# ChessMateBattery.net
KiCad netlist of a schematic drawn in EAGLE
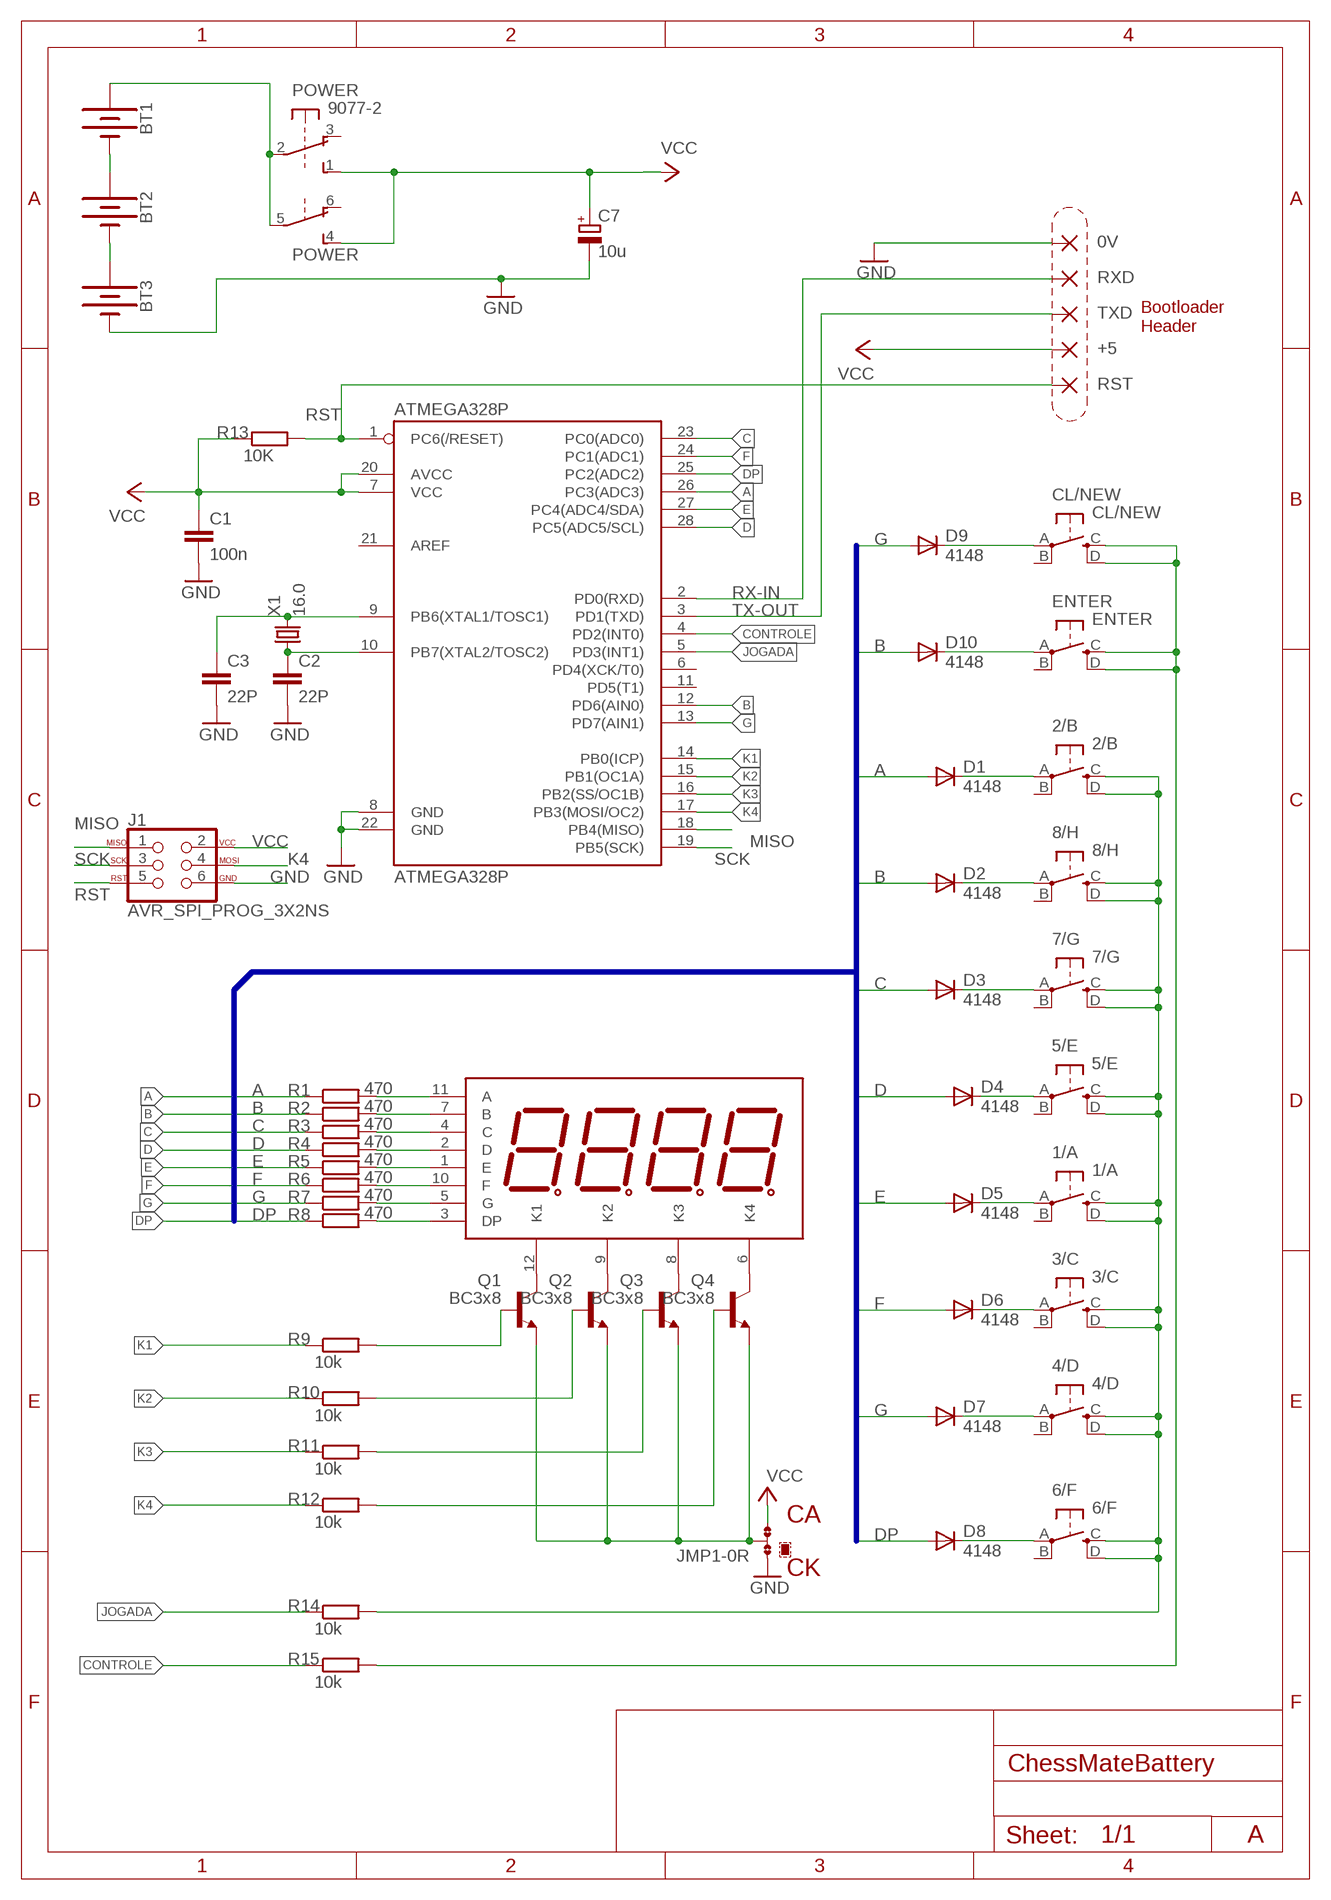
[diagram p0: schematic, sheet 1]

(export (version "E")
  (design (tool "Eeschema 10.0.6"))
  (components
    (comp (ref "+5")
      (value "2,15/1,0")
      (footprint "eagle-import:2,15_1,0")
      (libsource (lib "eagle-import") (part "2,15/1,0"))
    )
    (comp (ref "0V")
      (value "2,15/1,0")
      (footprint "eagle-import:2,15_1,0")
      (libsource (lib "eagle-import") (part "2,15/1,0"))
    )
    (comp (ref "1/A")
      (value "1/A")
      (footprint "eagle-import:TACT_SW")
      (libsource (lib "eagle-import") (part "10-XXTACT"))
    )
    (comp (ref "2/B")
      (value "2/B")
      (footprint "eagle-import:TACT_SW")
      (libsource (lib "eagle-import") (part "10-XXTACT"))
    )
    (comp (ref "3/C")
      (value "3/C")
      (footprint "eagle-import:TACT_SW")
      (libsource (lib "eagle-import") (part "10-XXTACT"))
    )
    (comp (ref "4/D")
      (value "4/D")
      (footprint "eagle-import:TACT_SW")
      (libsource (lib "eagle-import") (part "10-XXTACT"))
    )
    (comp (ref "5/E")
      (value "5/E")
      (footprint "eagle-import:TACT_SW")
      (libsource (lib "eagle-import") (part "10-XXTACT"))
    )
    (comp (ref "6/F")
      (value "6/F")
      (footprint "eagle-import:TACT_SW")
      (libsource (lib "eagle-import") (part "10-XXTACT"))
    )
    (comp (ref "7/G")
      (value "7/G")
      (footprint "eagle-import:TACT_SW")
      (libsource (lib "eagle-import") (part "10-XXTACT"))
    )
    (comp (ref "8/H")
      (value "8/H")
      (footprint "eagle-import:TACT_SW")
      (libsource (lib "eagle-import") (part "10-XXTACT"))
    )
    (comp (ref "ATMEGA328P")
      (value "ATMEGA328P")
      (footprint "eagle-import:DIL28-3")
      (libsource (lib "eagle-import") (part "ATMEGA328P_PDIP"))
    )
    (comp (ref "BT1")
      (value "BATTERY-AAA_KIT")
      (footprint "eagle-import:BATTERY-AAA-KIT")
      (libsource (lib "eagle-import") (part "BATTERY-AAA_KIT"))
    )
    (comp (ref "BT2")
      (value "BATTERY-AAA_KIT")
      (footprint "eagle-import:BATTERY-AAA-KIT")
      (libsource (lib "eagle-import") (part "BATTERY-AAA_KIT"))
    )
    (comp (ref "BT3")
      (value "BATTERY-AAA_KIT")
      (footprint "eagle-import:BATTERY-AAA-KIT")
      (libsource (lib "eagle-import") (part "BATTERY-AAA_KIT"))
    )
    (comp (ref "C1")
      (value "100n")
      (footprint "eagle-import:C050-024X044L")
      (libsource (lib "eagle-import") (part "C-EUC050-024X044L"))
    )
    (comp (ref "C2")
      (value "22P")
      (footprint "eagle-import:C025-024X044L")
      (libsource (lib "eagle-import") (part "C-EU"))
    )
    (comp (ref "C3")
      (value "22P")
      (footprint "eagle-import:C025-024X044L")
      (libsource (lib "eagle-import") (part "C-EU"))
    )
    (comp (ref "C7")
      (value "10u")
      (footprint "eagle-import:TT2D7L")
      (libsource (lib "eagle-import") (part "CPOL-EUTT2D7L"))
    )
    (comp (ref "CL/NEW")
      (value "CL/NEW")
      (footprint "eagle-import:TACT_SW")
      (libsource (lib "eagle-import") (part "10-XXTACT"))
    )
    (comp (ref "D1")
      (value "4148")
      (footprint "eagle-import:DO35-7")
      (libsource (lib "eagle-import") (part "1N4148DO35-7"))
    )
    (comp (ref "D2")
      (value "4148")
      (footprint "eagle-import:DO35-7")
      (libsource (lib "eagle-import") (part "1N4148DO35-7"))
    )
    (comp (ref "D3")
      (value "4148")
      (footprint "eagle-import:DO35-7")
      (libsource (lib "eagle-import") (part "1N4148DO35-7"))
    )
    (comp (ref "D4")
      (value "4148")
      (footprint "eagle-import:DO35-7")
      (libsource (lib "eagle-import") (part "1N4148DO35-7"))
    )
    (comp (ref "D5")
      (value "4148")
      (footprint "eagle-import:DO35-7")
      (libsource (lib "eagle-import") (part "1N4148DO35-7"))
    )
    (comp (ref "D6")
      (value "4148")
      (footprint "eagle-import:DO35-7")
      (libsource (lib "eagle-import") (part "1N4148DO35-7"))
    )
    (comp (ref "D7")
      (value "4148")
      (footprint "eagle-import:DO35-7")
      (libsource (lib "eagle-import") (part "1N4148DO35-7"))
    )
    (comp (ref "D8")
      (value "4148")
      (footprint "eagle-import:DO35-7")
      (libsource (lib "eagle-import") (part "1N4148DO35-7"))
    )
    (comp (ref "D9")
      (value "4148")
      (footprint "eagle-import:DO35-7")
      (libsource (lib "eagle-import") (part "1N4148DO35-7"))
    )
    (comp (ref "D10")
      (value "4148")
      (footprint "eagle-import:DO35-7")
      (libsource (lib "eagle-import") (part "1N4148DO35-7"))
    )
    (comp (ref "DISPLAY")
      (value "4_DIGIT-TOF3461BH-N")
      (footprint "eagle-import:TOF3461BH-N")
      (libsource (lib "eagle-import") (part "4_DIGIT-TOF3461BH-N"))
    )
    (comp (ref "ENTER")
      (value "ENTER")
      (footprint "eagle-import:TACT_SW")
      (libsource (lib "eagle-import") (part "10-XXTACT"))
    )
    (comp (ref "J1")
      (value "AVR_SPI_PROG_3X2NS")
      (footprint "eagle-import:2X3-NS")
      (libsource (lib "eagle-import") (part "AVR_SPI_PROG_3X2NS"))
    )
    (comp (ref "JMP1")
      (value "0R-JUMPA")
      (footprint "eagle-import:A0R-JMP")
      (libsource (lib "eagle-import") (part "0R-JUMPA"))
    )
    (comp (ref "POWER")
      (value "9077-2")
      (footprint "eagle-import:9077-2")
      (libsource (lib "eagle-import") (part "9077-2"))
    )
    (comp (ref "Q1")
      (value "BC3x8")
      (footprint "eagle-import:TO92-EBC")
      (libsource (lib "eagle-import") (part "BC338"))
    )
    (comp (ref "Q2")
      (value "BC3x8")
      (footprint "eagle-import:TO92-EBC")
      (libsource (lib "eagle-import") (part "BC338"))
    )
    (comp (ref "Q3")
      (value "BC3x8")
      (footprint "eagle-import:TO92-EBC")
      (libsource (lib "eagle-import") (part "BC338"))
    )
    (comp (ref "Q4")
      (value "BC3x8")
      (footprint "eagle-import:TO92-EBC")
      (libsource (lib "eagle-import") (part "BC338"))
    )
    (comp (ref "R1")
      (value "470")
      (footprint "eagle-import:0204_7L")
      (libsource (lib "eagle-import") (part "R-EU_0204/7L"))
    )
    (comp (ref "R2")
      (value "470")
      (footprint "eagle-import:0204_7L")
      (libsource (lib "eagle-import") (part "R-EU_0204/7L"))
    )
    (comp (ref "R3")
      (value "470")
      (footprint "eagle-import:0204_7L")
      (libsource (lib "eagle-import") (part "R-EU_0204/7L"))
    )
    (comp (ref "R4")
      (value "470")
      (footprint "eagle-import:0204_7L")
      (libsource (lib "eagle-import") (part "R-EU_0204/7L"))
    )
    (comp (ref "R5")
      (value "470")
      (footprint "eagle-import:0204_7L")
      (libsource (lib "eagle-import") (part "R-EU_0204/7L"))
    )
    (comp (ref "R6")
      (value "470")
      (footprint "eagle-import:0204_7L")
      (libsource (lib "eagle-import") (part "R-EU_0204/7L"))
    )
    (comp (ref "R7")
      (value "470")
      (footprint "eagle-import:0204_7L")
      (libsource (lib "eagle-import") (part "R-EU_0204/7L"))
    )
    (comp (ref "R8")
      (value "470")
      (footprint "eagle-import:0204_7L")
      (libsource (lib "eagle-import") (part "R-EU_0204/7L"))
    )
    (comp (ref "R9")
      (value "10k")
      (footprint "eagle-import:0204_7L")
      (libsource (lib "eagle-import") (part "R-EU_0204/7L"))
    )
    (comp (ref "R10")
      (value "10k")
      (footprint "eagle-import:0204_7L")
      (libsource (lib "eagle-import") (part "R-EU_0204/7L"))
    )
    (comp (ref "R11")
      (value "10k")
      (footprint "eagle-import:0204_7L")
      (libsource (lib "eagle-import") (part "R-EU_0204/7L"))
    )
    (comp (ref "R12")
      (value "10k")
      (footprint "eagle-import:0204_7L")
      (libsource (lib "eagle-import") (part "R-EU_0204/7L"))
    )
    (comp (ref "R13")
      (value "10K")
      (footprint "eagle-import:0204_5L")
      (libsource (lib "eagle-import") (part "R-EU_0204/5L"))
    )
    (comp (ref "R14")
      (value "10k")
      (footprint "eagle-import:0204_7L")
      (libsource (lib "eagle-import") (part "R-EU_0204/7L"))
    )
    (comp (ref "R15")
      (value "10k")
      (footprint "eagle-import:0204_7L")
      (libsource (lib "eagle-import") (part "R-EU_0204/7L"))
    )
    (comp (ref "RST")
      (value "2,15/1,0")
      (footprint "eagle-import:2,15_1,0")
      (libsource (lib "eagle-import") (part "2,15/1,0"))
    )
    (comp (ref "RXD")
      (value "2,15/1,0")
      (footprint "eagle-import:2,15_1,0")
      (libsource (lib "eagle-import") (part "2,15/1,0"))
    )
    (comp (ref "TXD")
      (value "2,15/1,0")
      (footprint "eagle-import:2,15_1,0")
      (libsource (lib "eagle-import") (part "2,15/1,0"))
    )
    (comp (ref "X1")
      (value "16.0")
      (footprint "eagle-import:HC49_SL")
      (libsource (lib "eagle-import") (part "CRYSTALHC49/SL"))
    )
  )
  (nets
    (net (code "1") (name "/MISO") (class "Default")
      (node (ref "ATMEGA328P") (pin "18") (pinfunction "PB4(MISO)_18") (pintype "bidirectional"))
      (node (ref "J1") (pin "1") (pinfunction "1_1") (pintype "passive"))
    )
    (net (code "2") (name "/RST") (class "Default")
      (node (ref "ATMEGA328P") (pin "1") (pinfunction "PC6(/RESET)_1") (pintype "bidirectional"))
      (node (ref "J1") (pin "5") (pinfunction "5_5") (pintype "passive"))
      (node (ref "R13") (pin "2") (pinfunction "2_2") (pintype "passive"))
      (node (ref "RST") (pin "1") (pinfunction "P_1") (pintype "passive"))
    )
    (net (code "3") (name "/RX-IN") (class "Default")
      (node (ref "ATMEGA328P") (pin "2") (pinfunction "PD0(RXD)_2") (pintype "bidirectional"))
      (node (ref "RXD") (pin "1") (pinfunction "P_1") (pintype "passive"))
    )
    (net (code "4") (name "/SCK") (class "Default")
      (node (ref "ATMEGA328P") (pin "19") (pinfunction "PB5(SCK)_19") (pintype "bidirectional"))
      (node (ref "J1") (pin "3") (pinfunction "3_3") (pintype "passive"))
    )
    (net (code "5") (name "/TX-OUT") (class "Default")
      (node (ref "ATMEGA328P") (pin "3") (pinfunction "PD1(TXD)_3") (pintype "bidirectional"))
      (node (ref "TXD") (pin "1") (pinfunction "P_1") (pintype "passive"))
    )
    (net (code "6") (name "A") (class "Default")
      (node (ref "ATMEGA328P") (pin "26") (pinfunction "PC3(ADC3)_26") (pintype "bidirectional"))
      (node (ref "D1") (pin "A") (pinfunction "A_A") (pintype "passive"))
      (node (ref "R1") (pin "1") (pinfunction "1_1") (pintype "passive"))
    )
    (net (code "7") (name "B") (class "Default")
      (node (ref "ATMEGA328P") (pin "12") (pinfunction "PD6(AIN0)_12") (pintype "bidirectional"))
      (node (ref "D10") (pin "A") (pinfunction "A_A") (pintype "passive"))
      (node (ref "D2") (pin "A") (pinfunction "A_A") (pintype "passive"))
      (node (ref "R2") (pin "1") (pinfunction "1_1") (pintype "passive"))
    )
    (net (code "8") (name "C") (class "Default")
      (node (ref "ATMEGA328P") (pin "23") (pinfunction "PC0(ADC0)_23") (pintype "bidirectional"))
      (node (ref "D3") (pin "A") (pinfunction "A_A") (pintype "passive"))
      (node (ref "R3") (pin "1") (pinfunction "1_1") (pintype "passive"))
    )
    (net (code "9") (name "CONTROLE") (class "Default")
      (node (ref "ATMEGA328P") (pin "4") (pinfunction "PD2(INT0)_4") (pintype "bidirectional"))
      (node (ref "R15") (pin "1") (pinfunction "1_1") (pintype "passive"))
    )
    (net (code "10") (name "D") (class "Default")
      (node (ref "ATMEGA328P") (pin "28") (pinfunction "PC5(ADC5/SCL)_28") (pintype "bidirectional"))
      (node (ref "D4") (pin "A") (pinfunction "A_A") (pintype "passive"))
      (node (ref "R4") (pin "1") (pinfunction "1_1") (pintype "passive"))
    )
    (net (code "11") (name "DP") (class "Default")
      (node (ref "ATMEGA328P") (pin "25") (pinfunction "PC2(ADC2)_25") (pintype "bidirectional"))
      (node (ref "D8") (pin "A") (pinfunction "A_A") (pintype "passive"))
      (node (ref "R8") (pin "1") (pinfunction "1_1") (pintype "passive"))
    )
    (net (code "12") (name "E") (class "Default")
      (node (ref "ATMEGA328P") (pin "27") (pinfunction "PC4(ADC4/SDA)_27") (pintype "bidirectional"))
      (node (ref "D5") (pin "A") (pinfunction "A_A") (pintype "passive"))
      (node (ref "R5") (pin "1") (pinfunction "1_1") (pintype "passive"))
    )
    (net (code "13") (name "F") (class "Default")
      (node (ref "ATMEGA328P") (pin "24") (pinfunction "PC1(ADC1)_24") (pintype "bidirectional"))
      (node (ref "D6") (pin "A") (pinfunction "A_A") (pintype "passive"))
      (node (ref "R6") (pin "1") (pinfunction "1_1") (pintype "passive"))
    )
    (net (code "14") (name "G") (class "Default")
      (node (ref "ATMEGA328P") (pin "13") (pinfunction "PD7(AIN1)_13") (pintype "bidirectional"))
      (node (ref "D7") (pin "A") (pinfunction "A_A") (pintype "passive"))
      (node (ref "D9") (pin "A") (pinfunction "A_A") (pintype "passive"))
      (node (ref "R7") (pin "1") (pinfunction "1_1") (pintype "passive"))
    )
    (net (code "15") (name "GND") (class "Default")
      (node (ref "0V") (pin "1") (pinfunction "P_1") (pintype "passive"))
      (node (ref "ATMEGA328P") (pin "22") (pinfunction "GND_22") (pintype "bidirectional"))
      (node (ref "ATMEGA328P") (pin "8") (pinfunction "GND_8") (pintype "bidirectional"))
      (node (ref "BT3") (pin "GND@1") (pinfunction "-_GND@1") (pintype "power_in"))
      (node (ref "C1") (pin "2") (pinfunction "2_2") (pintype "passive"))
      (node (ref "C2") (pin "2") (pinfunction "2_2") (pintype "passive"))
      (node (ref "C3") (pin "2") (pinfunction "2_2") (pintype "passive"))
      (node (ref "C7") (pin "-") (pinfunction "-_-") (pintype "passive"))
      (node (ref "J1") (pin "6") (pinfunction "6_6") (pintype "passive"))
      (node (ref "JMP1") (pin "1") (pinfunction "1_1") (pintype "passive"))
    )
    (net (code "16") (name "JOGADA") (class "Default")
      (node (ref "ATMEGA328P") (pin "5") (pinfunction "PD3(INT1)_5") (pintype "bidirectional"))
      (node (ref "R14") (pin "1") (pinfunction "1_1") (pintype "passive"))
    )
    (net (code "17") (name "K1") (class "Default")
      (node (ref "ATMEGA328P") (pin "14") (pinfunction "PB0(ICP)_14") (pintype "bidirectional"))
      (node (ref "R9") (pin "1") (pinfunction "1_1") (pintype "passive"))
    )
    (net (code "18") (name "K2") (class "Default")
      (node (ref "ATMEGA328P") (pin "15") (pinfunction "PB1(OC1A)_15") (pintype "bidirectional"))
      (node (ref "R10") (pin "1") (pinfunction "1_1") (pintype "passive"))
    )
    (net (code "19") (name "K3") (class "Default")
      (node (ref "ATMEGA328P") (pin "16") (pinfunction "PB2(SS/OC1B)_16") (pintype "bidirectional"))
      (node (ref "R11") (pin "1") (pinfunction "1_1") (pintype "passive"))
    )
    (net (code "20") (name "K4") (class "Default")
      (node (ref "ATMEGA328P") (pin "17") (pinfunction "PB3(MOSI/OC2)_17") (pintype "bidirectional"))
      (node (ref "J1") (pin "4") (pinfunction "4_4") (pintype "passive"))
      (node (ref "R12") (pin "1") (pinfunction "1_1") (pintype "passive"))
    )
    (net (code "21") (name "Net-(1/A-P)") (class "Default")
      (node (ref "1/A") (pin "A") (pinfunction "P_A") (pintype "passive"))
      (node (ref "D5") (pin "C") (pinfunction "C_C") (pintype "passive"))
    )
    (net (code "22") (name "Net-(1/A-S)") (class "Default")
      (node (ref "1/A") (pin "C") (pinfunction "S_C") (pintype "passive"))
      (node (ref "1/A") (pin "D") (pinfunction "S1_D") (pintype "passive"))
      (node (ref "2/B") (pin "C") (pinfunction "S_C") (pintype "passive"))
      (node (ref "2/B") (pin "D") (pinfunction "S1_D") (pintype "passive"))
      (node (ref "3/C") (pin "C") (pinfunction "S_C") (pintype "passive"))
      (node (ref "3/C") (pin "D") (pinfunction "S1_D") (pintype "passive"))
      (node (ref "4/D") (pin "C") (pinfunction "S_C") (pintype "passive"))
      (node (ref "4/D") (pin "D") (pinfunction "S1_D") (pintype "passive"))
      (node (ref "5/E") (pin "C") (pinfunction "S_C") (pintype "passive"))
      (node (ref "5/E") (pin "D") (pinfunction "S1_D") (pintype "passive"))
      (node (ref "6/F") (pin "C") (pinfunction "S_C") (pintype "passive"))
      (node (ref "6/F") (pin "D") (pinfunction "S1_D") (pintype "passive"))
      (node (ref "7/G") (pin "C") (pinfunction "S_C") (pintype "passive"))
      (node (ref "7/G") (pin "D") (pinfunction "S1_D") (pintype "passive"))
      (node (ref "8/H") (pin "C") (pinfunction "S_C") (pintype "passive"))
      (node (ref "8/H") (pin "D") (pinfunction "S1_D") (pintype "passive"))
      (node (ref "R14") (pin "2") (pinfunction "2_2") (pintype "passive"))
    )
    (net (code "23") (name "Net-(2/B-P)") (class "Default")
      (node (ref "2/B") (pin "A") (pinfunction "P_A") (pintype "passive"))
      (node (ref "D1") (pin "C") (pinfunction "C_C") (pintype "passive"))
    )
    (net (code "24") (name "Net-(3/C-P)") (class "Default")
      (node (ref "3/C") (pin "A") (pinfunction "P_A") (pintype "passive"))
      (node (ref "D6") (pin "C") (pinfunction "C_C") (pintype "passive"))
    )
    (net (code "25") (name "Net-(4/D-P)") (class "Default")
      (node (ref "4/D") (pin "A") (pinfunction "P_A") (pintype "passive"))
      (node (ref "D7") (pin "C") (pinfunction "C_C") (pintype "passive"))
    )
    (net (code "26") (name "Net-(5/E-P)") (class "Default")
      (node (ref "5/E") (pin "A") (pinfunction "P_A") (pintype "passive"))
      (node (ref "D4") (pin "C") (pinfunction "C_C") (pintype "passive"))
    )
    (net (code "27") (name "Net-(6/F-P)") (class "Default")
      (node (ref "6/F") (pin "A") (pinfunction "P_A") (pintype "passive"))
      (node (ref "D8") (pin "C") (pinfunction "C_C") (pintype "passive"))
    )
    (net (code "28") (name "Net-(7/G-P)") (class "Default")
      (node (ref "7/G") (pin "A") (pinfunction "P_A") (pintype "passive"))
      (node (ref "D3") (pin "C") (pinfunction "C_C") (pintype "passive"))
    )
    (net (code "29") (name "Net-(8/H-P)") (class "Default")
      (node (ref "8/H") (pin "A") (pinfunction "P_A") (pintype "passive"))
      (node (ref "D2") (pin "C") (pinfunction "C_C") (pintype "passive"))
    )
    (net (code "30") (name "Net-(ATMEGA328P-PB6(XTAL1{slash}TOSC1))") (class "Default")
      (node (ref "ATMEGA328P") (pin "9") (pinfunction "PB6(XTAL1/TOSC1)_9") (pintype "bidirectional"))
      (node (ref "C3") (pin "1") (pinfunction "1_1") (pintype "passive"))
      (node (ref "X1") (pin "2") (pinfunction "2_2") (pintype "passive"))
    )
    (net (code "31") (name "Net-(ATMEGA328P-PB7(XTAL2{slash}TOSC2))") (class "Default")
      (node (ref "ATMEGA328P") (pin "10") (pinfunction "PB7(XTAL2/TOSC2)_10") (pintype "bidirectional"))
      (node (ref "C2") (pin "1") (pinfunction "1_1") (pintype "passive"))
      (node (ref "X1") (pin "1") (pinfunction "1_1") (pintype "passive"))
    )
    (net (code "32") (name "Net-(BT1-+)") (class "Default")
      (node (ref "BT1") (pin "PWR@1") (pinfunction "+_PWR@1") (pintype "power_in"))
      (node (ref "POWER") (pin "2") (pinfunction "P_2") (pintype "passive"))
      (node (ref "POWER") (pin "5") (pinfunction "P_5") (pintype "passive"))
    )
    (net (code "33") (name "Net-(BT1--)") (class "Default")
      (node (ref "BT1") (pin "GND@1") (pinfunction "-_GND@1") (pintype "power_in"))
      (node (ref "BT2") (pin "PWR@1") (pinfunction "+_PWR@1") (pintype "power_in"))
    )
    (net (code "34") (name "Net-(BT2--)") (class "Default")
      (node (ref "BT2") (pin "GND@1") (pinfunction "-_GND@1") (pintype "power_in"))
      (node (ref "BT3") (pin "PWR@1") (pinfunction "+_PWR@1") (pintype "power_in"))
    )
    (net (code "35") (name "Net-(CL/NEW-P)") (class "Default")
      (node (ref "CL/NEW") (pin "A") (pinfunction "P_A") (pintype "passive"))
      (node (ref "D9") (pin "C") (pinfunction "C_C") (pintype "passive"))
    )
    (net (code "36") (name "Net-(CL/NEW-S)") (class "Default")
      (node (ref "CL/NEW") (pin "C") (pinfunction "S_C") (pintype "passive"))
      (node (ref "CL/NEW") (pin "D") (pinfunction "S1_D") (pintype "passive"))
      (node (ref "ENTER") (pin "C") (pinfunction "S_C") (pintype "passive"))
      (node (ref "ENTER") (pin "D") (pinfunction "S1_D") (pintype "passive"))
      (node (ref "R15") (pin "2") (pinfunction "2_2") (pintype "passive"))
    )
    (net (code "37") (name "Net-(DISPLAY-A)") (class "Default")
      (node (ref "DISPLAY") (pin "11") (pinfunction "A_11") (pintype "input"))
      (node (ref "R1") (pin "2") (pinfunction "2_2") (pintype "passive"))
    )
    (net (code "38") (name "Net-(DISPLAY-B)") (class "Default")
      (node (ref "DISPLAY") (pin "7") (pinfunction "B_7") (pintype "input"))
      (node (ref "R2") (pin "2") (pinfunction "2_2") (pintype "passive"))
    )
    (net (code "39") (name "Net-(DISPLAY-C)") (class "Default")
      (node (ref "DISPLAY") (pin "4") (pinfunction "C_4") (pintype "input"))
      (node (ref "R3") (pin "2") (pinfunction "2_2") (pintype "passive"))
    )
    (net (code "40") (name "Net-(DISPLAY-D)") (class "Default")
      (node (ref "DISPLAY") (pin "2") (pinfunction "D_2") (pintype "input"))
      (node (ref "R4") (pin "2") (pinfunction "2_2") (pintype "passive"))
    )
    (net (code "41") (name "Net-(DISPLAY-DP)") (class "Default")
      (node (ref "DISPLAY") (pin "3") (pinfunction "DP_3") (pintype "input"))
      (node (ref "R8") (pin "2") (pinfunction "2_2") (pintype "passive"))
    )
    (net (code "42") (name "Net-(DISPLAY-E)") (class "Default")
      (node (ref "DISPLAY") (pin "1") (pinfunction "E_1") (pintype "input"))
      (node (ref "R5") (pin "2") (pinfunction "2_2") (pintype "passive"))
    )
    (net (code "43") (name "Net-(DISPLAY-F)") (class "Default")
      (node (ref "DISPLAY") (pin "10") (pinfunction "F_10") (pintype "input"))
      (node (ref "R6") (pin "2") (pinfunction "2_2") (pintype "passive"))
    )
    (net (code "44") (name "Net-(DISPLAY-G)") (class "Default")
      (node (ref "DISPLAY") (pin "5") (pinfunction "G_5") (pintype "input"))
      (node (ref "R7") (pin "2") (pinfunction "2_2") (pintype "passive"))
    )
    (net (code "45") (name "Net-(DISPLAY-K1)") (class "Default")
      (node (ref "DISPLAY") (pin "12") (pinfunction "K1_12") (pintype "input"))
      (node (ref "Q1") (pin "C") (pinfunction "C_C") (pintype "passive"))
    )
    (net (code "46") (name "Net-(DISPLAY-K2)") (class "Default")
      (node (ref "DISPLAY") (pin "9") (pinfunction "K2_9") (pintype "input"))
      (node (ref "Q2") (pin "C") (pinfunction "C_C") (pintype "passive"))
    )
    (net (code "47") (name "Net-(DISPLAY-K3)") (class "Default")
      (node (ref "DISPLAY") (pin "8") (pinfunction "K3_8") (pintype "input"))
      (node (ref "Q3") (pin "C") (pinfunction "C_C") (pintype "passive"))
    )
    (net (code "48") (name "Net-(DISPLAY-K4)") (class "Default")
      (node (ref "DISPLAY") (pin "6") (pinfunction "K4_6") (pintype "input"))
      (node (ref "Q4") (pin "C") (pinfunction "C_C") (pintype "passive"))
    )
    (net (code "49") (name "Net-(ENTER-P)") (class "Default")
      (node (ref "D10") (pin "C") (pinfunction "C_C") (pintype "passive"))
      (node (ref "ENTER") (pin "A") (pinfunction "P_A") (pintype "passive"))
    )
    (net (code "50") (name "Net-(JMP1-Pad2)") (class "Default")
      (node (ref "JMP1") (pin "2") (pinfunction "2_2") (pintype "passive"))
      (node (ref "Q1") (pin "E") (pinfunction "E_E") (pintype "passive"))
      (node (ref "Q2") (pin "E") (pinfunction "E_E") (pintype "passive"))
      (node (ref "Q3") (pin "E") (pinfunction "E_E") (pintype "passive"))
      (node (ref "Q4") (pin "E") (pinfunction "E_E") (pintype "passive"))
    )
    (net (code "51") (name "Net-(Q1-PadB)") (class "Default")
      (node (ref "Q1") (pin "B") (pinfunction "B_B") (pintype "passive"))
      (node (ref "R9") (pin "2") (pinfunction "2_2") (pintype "passive"))
    )
    (net (code "52") (name "Net-(Q2-PadB)") (class "Default")
      (node (ref "Q2") (pin "B") (pinfunction "B_B") (pintype "passive"))
      (node (ref "R10") (pin "2") (pinfunction "2_2") (pintype "passive"))
    )
    (net (code "53") (name "Net-(Q3-PadB)") (class "Default")
      (node (ref "Q3") (pin "B") (pinfunction "B_B") (pintype "passive"))
      (node (ref "R11") (pin "2") (pinfunction "2_2") (pintype "passive"))
    )
    (net (code "54") (name "Net-(Q4-PadB)") (class "Default")
      (node (ref "Q4") (pin "B") (pinfunction "B_B") (pintype "passive"))
      (node (ref "R12") (pin "2") (pinfunction "2_2") (pintype "passive"))
    )
    (net (code "55") (name "VCC") (class "Default")
      (node (ref "+5") (pin "1") (pinfunction "P_1") (pintype "passive"))
      (node (ref "ATMEGA328P") (pin "20") (pinfunction "AVCC_20") (pintype "bidirectional"))
      (node (ref "ATMEGA328P") (pin "7") (pinfunction "VCC_7") (pintype "bidirectional"))
      (node (ref "C1") (pin "1") (pinfunction "1_1") (pintype "passive"))
      (node (ref "C7") (pin "+") (pinfunction "+_+") (pintype "passive"))
      (node (ref "J1") (pin "2") (pinfunction "2_2") (pintype "passive"))
      (node (ref "JMP1") (pin "3") (pinfunction "3_3") (pintype "passive"))
      (node (ref "POWER") (pin "1") (pinfunction "S_1") (pintype "passive"))
      (node (ref "POWER") (pin "4") (pinfunction "S_4") (pintype "passive"))
      (node (ref "R13") (pin "1") (pinfunction "1_1") (pintype "passive"))
    )
    (net (code "56") (name "unconnected-(1/A-P1-PadB)") (class "Default")
      (node (ref "1/A") (pin "B") (pinfunction "P1_B") (pintype "passive"))
    )
    (net (code "57") (name "unconnected-(2/B-P1-PadB)") (class "Default")
      (node (ref "2/B") (pin "B") (pinfunction "P1_B") (pintype "passive"))
    )
    (net (code "58") (name "unconnected-(3/C-P1-PadB)") (class "Default")
      (node (ref "3/C") (pin "B") (pinfunction "P1_B") (pintype "passive"))
    )
    (net (code "59") (name "unconnected-(4/D-P1-PadB)") (class "Default")
      (node (ref "4/D") (pin "B") (pinfunction "P1_B") (pintype "passive"))
    )
    (net (code "60") (name "unconnected-(5/E-P1-PadB)") (class "Default")
      (node (ref "5/E") (pin "B") (pinfunction "P1_B") (pintype "passive"))
    )
    (net (code "61") (name "unconnected-(6/F-P1-PadB)") (class "Default")
      (node (ref "6/F") (pin "B") (pinfunction "P1_B") (pintype "passive"))
    )
    (net (code "62") (name "unconnected-(7/G-P1-PadB)") (class "Default")
      (node (ref "7/G") (pin "B") (pinfunction "P1_B") (pintype "passive"))
    )
    (net (code "63") (name "unconnected-(8/H-P1-PadB)") (class "Default")
      (node (ref "8/H") (pin "B") (pinfunction "P1_B") (pintype "passive"))
    )
    (net (code "64") (name "unconnected-(ATMEGA328P-AREF-Pad21)") (class "Default")
      (node (ref "ATMEGA328P") (pin "21") (pinfunction "AREF_21") (pintype "bidirectional"))
    )
    (net (code "65") (name "unconnected-(ATMEGA328P-PD4(XCK{slash}T0)-Pad6)") (class "Default")
      (node (ref "ATMEGA328P") (pin "6") (pinfunction "PD4(XCK/T0)_6") (pintype "bidirectional"))
    )
    (net (code "66") (name "unconnected-(ATMEGA328P-PD5(T1)-Pad11)") (class "Default")
      (node (ref "ATMEGA328P") (pin "11") (pinfunction "PD5(T1)_11") (pintype "bidirectional"))
    )
    (net (code "67") (name "unconnected-(CL/NEW-P1-PadB)") (class "Default")
      (node (ref "CL/NEW") (pin "B") (pinfunction "P1_B") (pintype "passive"))
    )
    (net (code "68") (name "unconnected-(ENTER-P1-PadB)") (class "Default")
      (node (ref "ENTER") (pin "B") (pinfunction "P1_B") (pintype "passive"))
    )
    (net (code "69") (name "unconnected-(POWERA-O-Pad3)") (class "Default")
      (node (ref "POWER") (pin "3") (pinfunction "O_3") (pintype "passive"))
    )
    (net (code "70") (name "unconnected-(POWERB-O-Pad6)") (class "Default")
      (node (ref "POWER") (pin "6") (pinfunction "O_6") (pintype "passive"))
    )
  )
)
